# MediumWaveRadioTransmitter.net
KiCad netlist of a schematic drawn in EAGLE
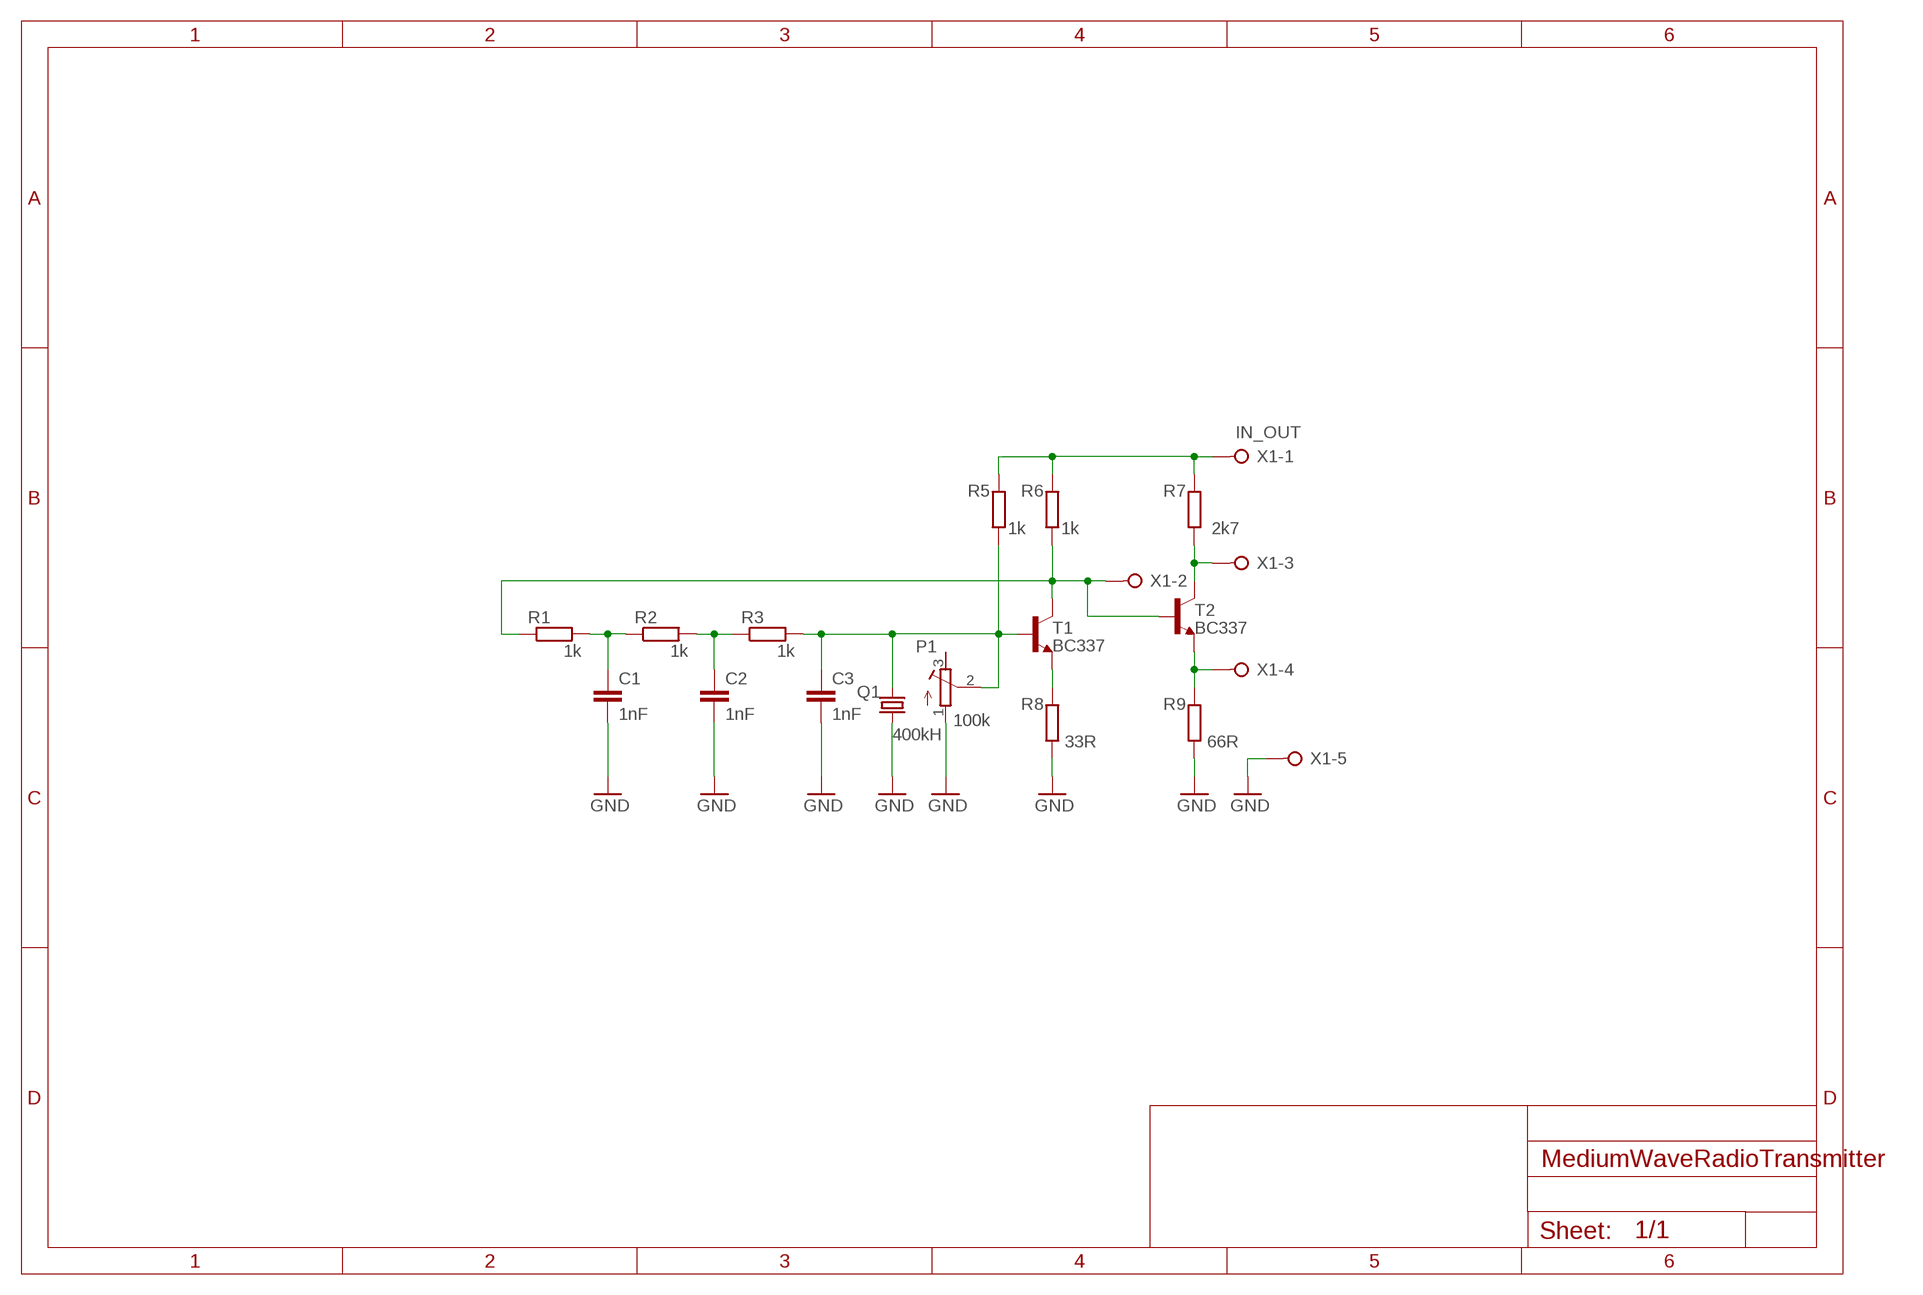
[diagram p0: schematic, sheet 1]

(export (version "E")
  (design (tool "Eeschema 10.0.6"))
  (components
    (comp (ref "C1")
      (value "1nF")
      (footprint "eagle-import:C050-024X044")
      (libsource (lib "eagle-import") (part "C-EU050-024X044"))
    )
    (comp (ref "C2")
      (value "1nF")
      (footprint "eagle-import:C050-024X044")
      (libsource (lib "eagle-import") (part "C-EU050-024X044"))
    )
    (comp (ref "C3")
      (value "1nF")
      (footprint "eagle-import:C050-024X044")
      (libsource (lib "eagle-import") (part "C-EU050-024X044"))
    )
    (comp (ref "P1")
      (value "100k")
      (footprint "eagle-import:RTRIM3296W")
      (libsource (lib "eagle-import") (part "R-TRIMM3296W"))
    )
    (comp (ref "Q1")
      (value "400kH")
      (footprint "eagle-import:HC18U-V")
      (libsource (lib "eagle-import") (part "CRYSTALHC18U-V"))
    )
    (comp (ref "R1")
      (value "1k")
      (footprint "eagle-import:0207_10")
      (libsource (lib "eagle-import") (part "R-EU_0207/10"))
    )
    (comp (ref "R2")
      (value "1k")
      (footprint "eagle-import:0207_10")
      (libsource (lib "eagle-import") (part "R-EU_0207/10"))
    )
    (comp (ref "R3")
      (value "1k")
      (footprint "eagle-import:0207_10")
      (libsource (lib "eagle-import") (part "R-EU_0207/10"))
    )
    (comp (ref "R5")
      (value "1k")
      (footprint "eagle-import:0207_10")
      (libsource (lib "eagle-import") (part "R-EU_0207/10"))
    )
    (comp (ref "R6")
      (value "1k")
      (footprint "eagle-import:0207_10")
      (libsource (lib "eagle-import") (part "R-EU_0207/10"))
    )
    (comp (ref "R7")
      (value "2k7")
      (footprint "eagle-import:0207_10")
      (libsource (lib "eagle-import") (part "R-EU_0207/10"))
    )
    (comp (ref "R8")
      (value "33R")
      (footprint "eagle-import:0207_10")
      (libsource (lib "eagle-import") (part "R-EU_0207/10"))
    )
    (comp (ref "R9")
      (value "66R")
      (footprint "eagle-import:0207_10")
      (libsource (lib "eagle-import") (part "R-EU_0207/10"))
    )
    (comp (ref "T1")
      (value "BC337")
      (footprint "eagle-import:TO92-CBE")
      (libsource (lib "eagle-import") (part "-NPN-TO92-CBEBC337-16"))
    )
    (comp (ref "T2")
      (value "BC337")
      (footprint "eagle-import:TO92-CBE")
      (libsource (lib "eagle-import") (part "-NPN-TO92-CBEBC337-16"))
    )
    (comp (ref "X1")
      (value "IN_OUT")
      (footprint "eagle-import:W237-5P")
      (libsource (lib "eagle-import") (part "W237-05P"))
    )
  )
  (nets
    (net (code "1") (name "GND") (class "Default")
      (node (ref "C1") (pin "2") (pinfunction "2_2") (pintype "passive"))
      (node (ref "C2") (pin "2") (pinfunction "2_2") (pintype "passive"))
      (node (ref "C3") (pin "2") (pinfunction "2_2") (pintype "passive"))
      (node (ref "P1") (pin "1") (pinfunction "A_1") (pintype "passive"))
      (node (ref "Q1") (pin "2") (pinfunction "2_2") (pintype "passive"))
      (node (ref "R8") (pin "1") (pinfunction "1_1") (pintype "passive"))
      (node (ref "R9") (pin "1") (pinfunction "1_1") (pintype "passive"))
      (node (ref "X1") (pin "5") (pinfunction "KL_5") (pintype "passive"))
    )
    (net (code "2") (name "Net-(C1-Pad1)") (class "Default")
      (node (ref "C1") (pin "1") (pinfunction "1_1") (pintype "passive"))
      (node (ref "R1") (pin "2") (pinfunction "2_2") (pintype "passive"))
      (node (ref "R2") (pin "1") (pinfunction "1_1") (pintype "passive"))
    )
    (net (code "3") (name "Net-(C2-Pad1)") (class "Default")
      (node (ref "C2") (pin "1") (pinfunction "1_1") (pintype "passive"))
      (node (ref "R2") (pin "2") (pinfunction "2_2") (pintype "passive"))
      (node (ref "R3") (pin "1") (pinfunction "1_1") (pintype "passive"))
    )
    (net (code "4") (name "Net-(P1-S)") (class "Default")
      (node (ref "C3") (pin "1") (pinfunction "1_1") (pintype "passive"))
      (node (ref "P1") (pin "2") (pinfunction "S_2") (pintype "passive"))
      (node (ref "Q1") (pin "1") (pinfunction "1_1") (pintype "passive"))
      (node (ref "R3") (pin "2") (pinfunction "2_2") (pintype "passive"))
      (node (ref "R5") (pin "1") (pinfunction "1_1") (pintype "passive"))
      (node (ref "T1") (pin "B") (pinfunction "B_B") (pintype "passive"))
    )
    (net (code "5") (name "Net-(R8-Pad2)") (class "Default")
      (node (ref "R8") (pin "2") (pinfunction "2_2") (pintype "passive"))
      (node (ref "T1") (pin "E") (pinfunction "E_E") (pintype "passive"))
    )
    (net (code "6") (name "Net-(X1A-KL)") (class "Default")
      (node (ref "R5") (pin "2") (pinfunction "2_2") (pintype "passive"))
      (node (ref "R6") (pin "2") (pinfunction "2_2") (pintype "passive"))
      (node (ref "R7") (pin "2") (pinfunction "2_2") (pintype "passive"))
      (node (ref "X1") (pin "1") (pinfunction "KL_1") (pintype "passive"))
    )
    (net (code "7") (name "Net-(X1B-KL)") (class "Default")
      (node (ref "R1") (pin "1") (pinfunction "1_1") (pintype "passive"))
      (node (ref "R6") (pin "1") (pinfunction "1_1") (pintype "passive"))
      (node (ref "T1") (pin "C") (pinfunction "C_C") (pintype "passive"))
      (node (ref "T2") (pin "B") (pinfunction "B_B") (pintype "passive"))
      (node (ref "X1") (pin "2") (pinfunction "KL_2") (pintype "passive"))
    )
    (net (code "8") (name "Net-(X1C-KL)") (class "Default")
      (node (ref "R7") (pin "1") (pinfunction "1_1") (pintype "passive"))
      (node (ref "T2") (pin "C") (pinfunction "C_C") (pintype "passive"))
      (node (ref "X1") (pin "3") (pinfunction "KL_3") (pintype "passive"))
    )
    (net (code "9") (name "Net-(X1D-KL)") (class "Default")
      (node (ref "R9") (pin "2") (pinfunction "2_2") (pintype "passive"))
      (node (ref "T2") (pin "E") (pinfunction "E_E") (pintype "passive"))
      (node (ref "X1") (pin "4") (pinfunction "KL_4") (pintype "passive"))
    )
    (net (code "10") (name "unconnected-(P1-E-Pad3)") (class "Default")
      (node (ref "P1") (pin "3") (pinfunction "E_3") (pintype "passive"))
    )
  )
)
